# Sigma_Delta.net
KiCad netlist of a schematic drawn in Altium Designer
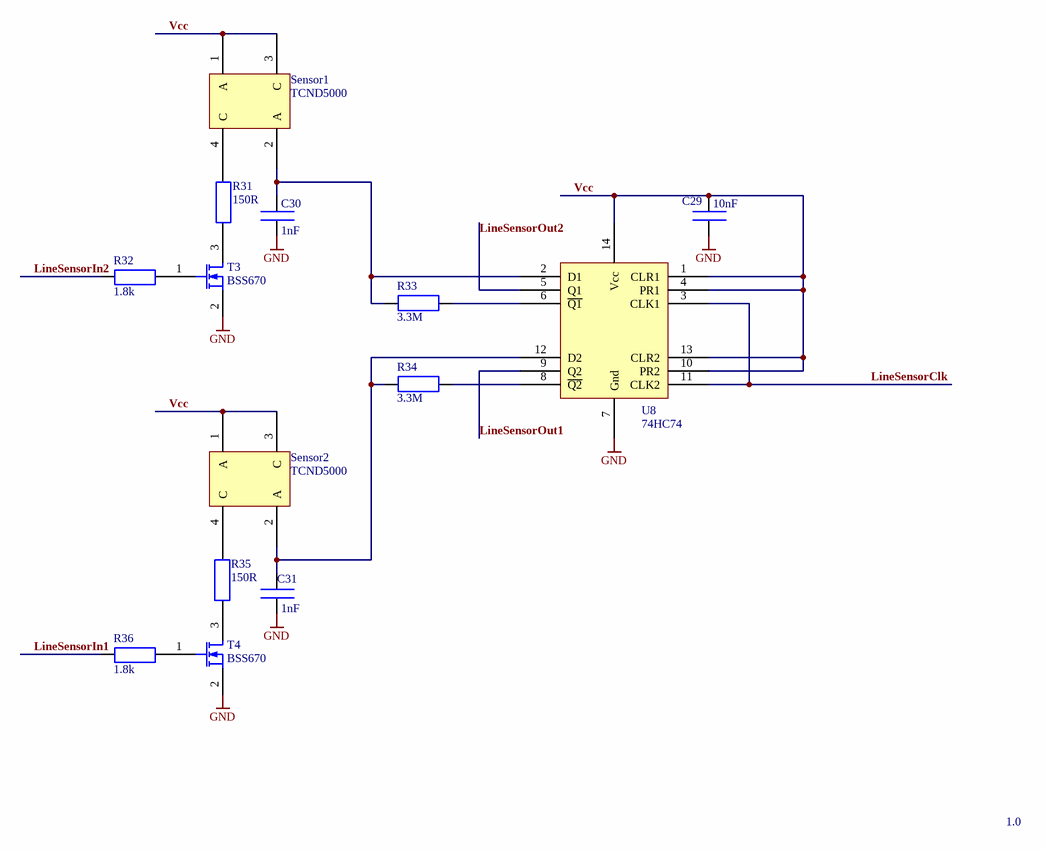
[diagram p0: Sigma_Delta.SCHDOC]

(export (version "E")
  (design (tool "Eeschema 10.0.6"))
  (components
    (comp (ref "C29")
      (value "10nF")
      (footprint "1608[0603]")
      (description "Capacitor")
      (fields
        (field (name "PART TYPE") "10nF")
        (field (name "MANUFACTURER") "AVX")
        (field (name "PART NUMBER") "06035C103KAT2A")
      )
      (libsource (lib "POWER_SUPPLY") (part "CAP"))
    )
    (comp (ref "C30")
      (value "1nF")
      (footprint "1608[0603]")
      (description "Capacitor")
      (fields
        (field (name "PART TYPE") "1nF")
        (field (name "MANUFACTURER") "Murata")
        (field (name "PART NUMBER") "GRM188R71H102KA01D")
      )
      (libsource (lib "POWER_SUPPLY") (part "CAP"))
    )
    (comp (ref "C31")
      (value "1nF")
      (footprint "1608[0603]")
      (description "Capacitor")
      (fields
        (field (name "PART TYPE") "1nF")
        (field (name "MANUFACTURER") "Murata")
        (field (name "PART NUMBER") "GRM188R71H102KA01D")
      )
      (libsource (lib "POWER_SUPPLY") (part "CAP"))
    )
    (comp (ref "R31")
      (value "150R")
      (footprint "1608[0603]")
      (description "Resistance")
      (fields
        (field (name "PART TYPE") "150R")
        (field (name "MANUFACTURER") "Multicomp")
        (field (name "PART NUMBER") "MC 0.063W 0603 1% 150R")
      )
      (libsource (lib "POWER_SUPPLY") (part "RES"))
    )
    (comp (ref "R32")
      (value "1.8k")
      (footprint "1608[0603]")
      (description "Resistance")
      (fields
        (field (name "PART TYPE") "1.8k")
        (field (name "MANUFACTURER") "Multicomp")
        (field (name "PART NUMBER") "MC 0.063W 0603 1% 1K8")
      )
      (libsource (lib "POWER_SUPPLY") (part "RES"))
    )
    (comp (ref "R33")
      (value "3.3M")
      (footprint "1608[0603]")
      (description "Resistance")
      (fields
        (field (name "PART TYPE") "3.3M")
        (field (name "MANUFACTURER") "PHYCOMP")
        (field (name "PART NUMBER") "232270463305")
      )
      (libsource (lib "POWER_SUPPLY") (part "RES"))
    )
    (comp (ref "R34")
      (value "3.3M")
      (footprint "1608[0603]")
      (description "Resistance")
      (fields
        (field (name "PART TYPE") "3.3M")
        (field (name "MANUFACTURER") "PHYCOMP")
        (field (name "PART NUMBER") "232270463305")
      )
      (libsource (lib "POWER_SUPPLY") (part "RES"))
    )
    (comp (ref "R35")
      (value "150R")
      (footprint "1608[0603]")
      (description "Resistance")
      (fields
        (field (name "PART TYPE") "150R")
        (field (name "MANUFACTURER") "Multicomp")
        (field (name "PART NUMBER") "MC 0.063W 0603 1% 150R")
      )
      (libsource (lib "POWER_SUPPLY") (part "RES"))
    )
    (comp (ref "R36")
      (value "1.8k")
      (footprint "1608[0603]")
      (description "Resistance")
      (fields
        (field (name "PART TYPE") "1.8k")
        (field (name "MANUFACTURER") "Multicomp")
        (field (name "PART NUMBER") "MC 0.063W 0603 1% 1K8")
      )
      (libsource (lib "POWER_SUPPLY") (part "RES"))
    )
    (comp (ref "Sensor1")
      (value "TCND5000")
      (footprint "TCND5000")
      (fields (field (name "MANUFACTURER") "Vishay"))
      (libsource (lib "Power_supply") (part "TCND5000"))
    )
    (comp (ref "Sensor2")
      (value "TCND5000")
      (footprint "TCND5000")
      (fields (field (name "MANUFACTURER") "Vishay"))
      (libsource (lib "Power_supply") (part "TCND5000"))
    )
    (comp (ref "T3")
      (value "BSS670")
      (footprint "Power_supply_library:SOT-23")
      (fields (field (name "MANUFACTURER") "Infineon") (field (name "PART NUMBER") "BSS670S2L"))
      (libsource (lib "Power_supply_library") (part "MOSFET-N"))
    )
    (comp (ref "T4")
      (value "BSS670")
      (footprint "Power_supply_library:SOT-23")
      (fields (field (name "MANUFACTURER") "Infineon") (field (name "PART NUMBER") "BSS670S2L"))
      (libsource (lib "Power_supply_library") (part "MOSFET-N"))
    )
    (comp (ref "U8")
      (value "74HC74")
      (footprint "SO-G14")
      (fields (field (name "MANUFACTURER") "TI") (field (name "PART NUMBER") "SN74HC74D"))
      (libsource (lib "Reflective") (part "74HC74"))
    )
  )
  (nets
    (net (code "1") (name "/LineSensorClk") (class "Default")
      (node (ref "U8") (pin "11") (pinfunction "CLK2_11") (pintype "passive"))
      (node (ref "U8") (pin "3") (pinfunction "CLK1_3") (pintype "passive"))
    )
    (net (code "2") (name "/LineSensorIn1") (class "Default")
      (node (ref "R36") (pin "1") (pinfunction "J1_1") (pintype "passive"))
    )
    (net (code "3") (name "/LineSensorIn2") (class "Default")
      (node (ref "R32") (pin "1") (pinfunction "J1_1") (pintype "passive"))
    )
    (net (code "4") (name "/LineSensorOut1") (class "Default")
      (node (ref "U8") (pin "9") (pinfunction "Q2_9") (pintype "passive"))
    )
    (net (code "5") (name "/LineSensorOut2") (class "Default")
      (node (ref "U8") (pin "5") (pinfunction "Q1_5") (pintype "passive"))
    )
    (net (code "6") (name "/Vcc") (class "Default")
      (node (ref "C29") (pin "2") (pinfunction "J2_2") (pintype "passive"))
      (node (ref "Sensor1") (pin "1") (pinfunction "A_1") (pintype "passive"))
      (node (ref "Sensor1") (pin "3") (pinfunction "C_3") (pintype "passive"))
      (node (ref "Sensor2") (pin "1") (pinfunction "A_1") (pintype "passive"))
      (node (ref "Sensor2") (pin "3") (pinfunction "C_3") (pintype "passive"))
      (node (ref "U8") (pin "1") (pinfunction "CLR1_1") (pintype "passive"))
      (node (ref "U8") (pin "10") (pinfunction "PR2_10") (pintype "passive"))
      (node (ref "U8") (pin "13") (pinfunction "CLR2_13") (pintype "passive"))
      (node (ref "U8") (pin "14") (pinfunction "Vcc_14") (pintype "passive"))
      (node (ref "U8") (pin "4") (pinfunction "PR1_4") (pintype "passive"))
    )
    (net (code "7") (name "GND") (class "Default")
      (node (ref "C29") (pin "1") (pinfunction "J1_1") (pintype "passive"))
      (node (ref "C30") (pin "1") (pinfunction "J1_1") (pintype "passive"))
      (node (ref "C31") (pin "1") (pinfunction "J1_1") (pintype "passive"))
      (node (ref "T3") (pin "2") (pinfunction "S_2") (pintype "passive"))
      (node (ref "T4") (pin "2") (pinfunction "S_2") (pintype "passive"))
      (node (ref "U8") (pin "7") (pinfunction "Gnd_7") (pintype "passive"))
    )
    (net (code "8") (name "Net-(C30-J2)") (class "Default")
      (node (ref "C30") (pin "2") (pinfunction "J2_2") (pintype "passive"))
      (node (ref "R33") (pin "2") (pinfunction "J2_2") (pintype "passive"))
      (node (ref "Sensor1") (pin "2") (pinfunction "A_2") (pintype "passive"))
      (node (ref "U8") (pin "2") (pinfunction "D1_2") (pintype "passive"))
    )
    (net (code "9") (name "Net-(C31-J2)") (class "Default")
      (node (ref "C31") (pin "2") (pinfunction "J2_2") (pintype "passive"))
      (node (ref "R34") (pin "2") (pinfunction "J2_2") (pintype "passive"))
      (node (ref "Sensor2") (pin "2") (pinfunction "A_2") (pintype "passive"))
      (node (ref "U8") (pin "12") (pinfunction "D2_12") (pintype "passive"))
    )
    (net (code "10") (name "Net-(R31-J1)") (class "Default")
      (node (ref "R31") (pin "1") (pinfunction "J1_1") (pintype "passive"))
      (node (ref "T3") (pin "3") (pinfunction "D_3") (pintype "passive"))
    )
    (net (code "11") (name "Net-(R31-J2)") (class "Default")
      (node (ref "R31") (pin "2") (pinfunction "J2_2") (pintype "passive"))
      (node (ref "Sensor1") (pin "4") (pinfunction "C_4") (pintype "passive"))
    )
    (net (code "12") (name "Net-(R32-J2)") (class "Default")
      (node (ref "R32") (pin "2") (pinfunction "J2_2") (pintype "passive"))
      (node (ref "T3") (pin "1") (pinfunction "G_1") (pintype "passive"))
    )
    (net (code "13") (name "Net-(R33-J1)") (class "Default")
      (node (ref "R33") (pin "1") (pinfunction "J1_1") (pintype "passive"))
      (node (ref "U8") (pin "6") (pinfunction "~{Q1}_6") (pintype "passive"))
    )
    (net (code "14") (name "Net-(R34-J1)") (class "Default")
      (node (ref "R34") (pin "1") (pinfunction "J1_1") (pintype "passive"))
      (node (ref "U8") (pin "8") (pinfunction "~{Q2}_8") (pintype "passive"))
    )
    (net (code "15") (name "Net-(R35-J1)") (class "Default")
      (node (ref "R35") (pin "1") (pinfunction "J1_1") (pintype "passive"))
      (node (ref "Sensor2") (pin "4") (pinfunction "C_4") (pintype "passive"))
    )
    (net (code "16") (name "Net-(R35-J2)") (class "Default")
      (node (ref "R35") (pin "2") (pinfunction "J2_2") (pintype "passive"))
      (node (ref "T4") (pin "3") (pinfunction "D_3") (pintype "passive"))
    )
    (net (code "17") (name "Net-(R36-J2)") (class "Default")
      (node (ref "R36") (pin "2") (pinfunction "J2_2") (pintype "passive"))
      (node (ref "T4") (pin "1") (pinfunction "G_1") (pintype "passive"))
    )
  )
)
